# ghc-silk.net
KiCad netlist of a schematic drawn in EAGLE
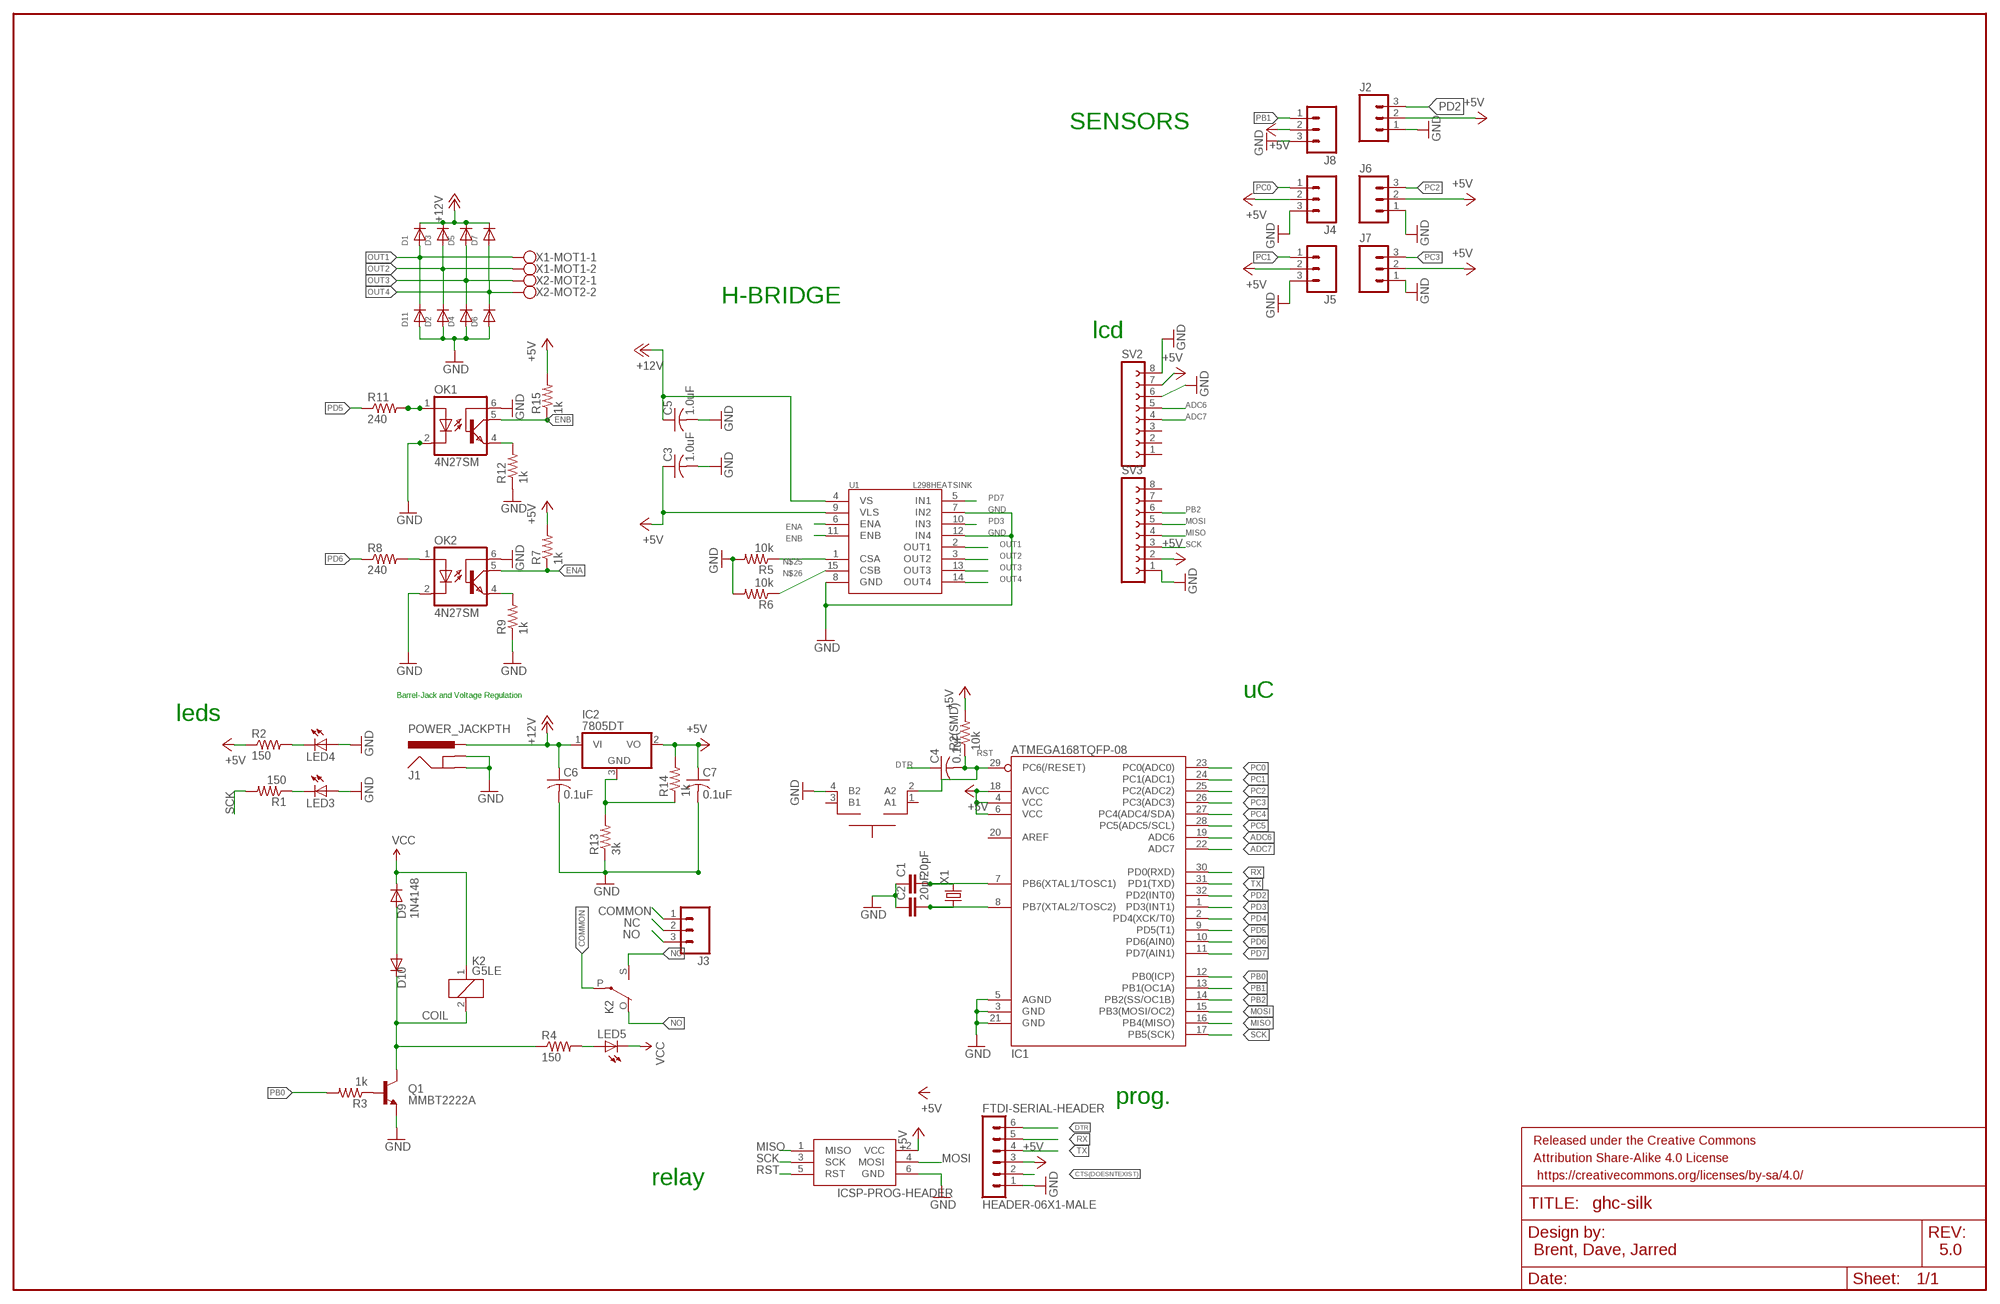
[diagram p0: schematic, sheet 1]

(export (version "E")
  (design (tool "Eeschema 10.0.6"))
  (components
    (comp (ref "C1")
      (value "20pF")
      (footprint "eagle-import:C0805")
      (libsource (lib "eagle-import") (part "C-EUC0805"))
    )
    (comp (ref "C2")
      (value "20pF")
      (footprint "eagle-import:C0805")
      (libsource (lib "eagle-import") (part "C-EUC0805"))
    )
    (comp (ref "C3")
      (value "1.0uF")
      (footprint "eagle-import:C0805")
      (libsource (lib "eagle-import") (part "C-USC0805"))
    )
    (comp (ref "C4")
      (value "0.1uF")
      (footprint "eagle-import:C0805")
      (libsource (lib "eagle-import") (part "C-USC0805"))
    )
    (comp (ref "C5")
      (value "1.0uF")
      (footprint "eagle-import:C0805")
      (libsource (lib "eagle-import") (part "C-USC0805"))
    )
    (comp (ref "C6")
      (value "0.1uF")
      (footprint "eagle-import:C0805")
      (libsource (lib "eagle-import") (part "C-USC0805"))
    )
    (comp (ref "C7")
      (value "0.1uF")
      (footprint "eagle-import:C0805")
      (libsource (lib "eagle-import") (part "C-USC0805"))
    )
    (comp (ref "D1")
      (value "DIODESOD-523")
      (footprint "eagle-import:SOD-523")
      (libsource (lib "eagle-import") (part "DIODESOD-523"))
    )
    (comp (ref "D2")
      (value "DIODESOD-523")
      (footprint "eagle-import:SOD-523")
      (libsource (lib "eagle-import") (part "DIODESOD-523"))
    )
    (comp (ref "D3")
      (value "DIODESOD-523")
      (footprint "eagle-import:SOD-523")
      (libsource (lib "eagle-import") (part "DIODESOD-523"))
    )
    (comp (ref "D4")
      (value "DIODESOD-523")
      (footprint "eagle-import:SOD-523")
      (libsource (lib "eagle-import") (part "DIODESOD-523"))
    )
    (comp (ref "D5")
      (value "DIODESOD-523")
      (footprint "eagle-import:SOD-523")
      (libsource (lib "eagle-import") (part "DIODESOD-523"))
    )
    (comp (ref "D6")
      (value "DIODESOD-523")
      (footprint "eagle-import:SOD-523")
      (libsource (lib "eagle-import") (part "DIODESOD-523"))
    )
    (comp (ref "D7")
      (value "DIODESOD-523")
      (footprint "eagle-import:SOD-523")
      (libsource (lib "eagle-import") (part "DIODESOD-523"))
    )
    (comp (ref "D9")
      (value "1N4148")
      (footprint "eagle-import:SOD-323F")
      (libsource (lib "eagle-import") (part "DIODESOD-323F"))
    )
    (comp (ref "D10")
      (value "Zener")
      (footprint "eagle-import:SOD-323F")
      (libsource (lib "eagle-import") (part "DIODESOD-323F"))
    )
    (comp (ref "D11")
      (value "DIODESOD-523")
      (footprint "eagle-import:SOD-523")
      (libsource (lib "eagle-import") (part "DIODESOD-523"))
    )
    (comp (ref "FRAME1")
      (value "FRAME-LEDGER")
      (footprint "eagle-import:CREATIVE_COMMONS")
      (libsource (lib "eagle-import") (part "FRAME-LEDGER"))
    )
    (comp (ref "FTDI-SERIAL-HEADER")
      (value "HEADER-06X1-MALE")
      (footprint "eagle-import:06X1-PTH")
      (libsource (lib "eagle-import") (part "HEADER-06X1?-MALE"))
    )
    (comp (ref "IC1")
      (value "ATMEGA168TQFP-08")
      (footprint "eagle-import:TQFP32-08")
      (libsource (lib "eagle-import") (part "ATMEGA168TQFP-08"))
    )
    (comp (ref "IC2")
      (value "7805DT")
      (footprint "eagle-import:TO252")
      (libsource (lib "eagle-import") (part "78DT05"))
    )
    (comp (ref "ICSP-PROG-HEADER")
      (value "AVRISP-6")
      (footprint "eagle-import:AVRISP")
      (libsource (lib "eagle-import") (part "AVRISP-6"))
    )
    (comp (ref "J1")
      (value "POWER_JACKPTH")
      (footprint "eagle-import:POWER_JACK_PTH")
      (libsource (lib "eagle-import") (part "POWER_JACKPTH"))
    )
    (comp (ref "J2")
      (value "M03SCREW_LOCK")
      (footprint "eagle-import:SCREWTERMINAL-3.5MM-3_LOCK.007S")
      (libsource (lib "eagle-import") (part "M03SCREW_LOCK"))
    )
    (comp (ref "J3")
      (value "M03-SCREW-5MM")
      (footprint "eagle-import:SCREWTERMINAL-5MM-3")
      (libsource (lib "eagle-import") (part "M03-SCREW-5MM"))
    )
    (comp (ref "J4")
      (value "M03SCREW_LOCK")
      (footprint "eagle-import:SCREWTERMINAL-3.5MM-3_LOCK.007S")
      (libsource (lib "eagle-import") (part "M03SCREW_LOCK"))
    )
    (comp (ref "J5")
      (value "M03SCREW_LOCK")
      (footprint "eagle-import:SCREWTERMINAL-3.5MM-3_LOCK.007S")
      (libsource (lib "eagle-import") (part "M03SCREW_LOCK"))
    )
    (comp (ref "J6")
      (value "M03SCREW_LOCK")
      (footprint "eagle-import:SCREWTERMINAL-3.5MM-3_LOCK.007S")
      (libsource (lib "eagle-import") (part "M03SCREW_LOCK"))
    )
    (comp (ref "J7")
      (value "M03SCREW_LOCK")
      (footprint "eagle-import:SCREWTERMINAL-3.5MM-3_LOCK.007S")
      (libsource (lib "eagle-import") (part "M03SCREW_LOCK"))
    )
    (comp (ref "J8")
      (value "M03SCREW_LOCK")
      (footprint "eagle-import:SCREWTERMINAL-3.5MM-3_LOCK.007S")
      (libsource (lib "eagle-import") (part "M03SCREW_LOCK"))
    )
    (comp (ref "K2")
      (value "G5LE")
      (footprint "eagle-import:G5LE")
      (libsource (lib "eagle-import") (part "G5LE"))
    )
    (comp (ref "LED3")
      (value "LEDCHIP-LED0805")
      (footprint "eagle-import:CHIP-LED0805")
      (libsource (lib "eagle-import") (part "LEDCHIP-LED0805"))
    )
    (comp (ref "LED4")
      (value "LEDCHIP-LED0805")
      (footprint "eagle-import:CHIP-LED0805")
      (libsource (lib "eagle-import") (part "LEDCHIP-LED0805"))
    )
    (comp (ref "LED5")
      (value "LEDCHIP-LED0805")
      (footprint "eagle-import:CHIP-LED0805")
      (libsource (lib "eagle-import") (part "LEDCHIP-LED0805"))
    )
    (comp (ref "OK1")
      (value "4N27SM")
      (footprint "eagle-import:DIL6-SMD")
      (fields (field (name "MF") "FAIRCHILD SEMICONDUCTOR") (field (name "MPN") "4N27S-M"))
      (libsource (lib "eagle-import") (part "4N?MS27"))
    )
    (comp (ref "OK2")
      (value "4N27SM")
      (footprint "eagle-import:DIL6-SMD")
      (fields (field (name "MF") "FAIRCHILD SEMICONDUCTOR") (field (name "MPN") "4N27S-M"))
      (libsource (lib "eagle-import") (part "4N?MS27"))
    )
    (comp (ref "Q1")
      (value "MMBT2222A")
      (footprint "eagle-import:SOT23-3")
      (libsource (lib "eagle-import") (part "TRANSISTOR_NPNMMBT2222A"))
    )
    (comp (ref "R1")
      (value "150")
      (footprint "eagle-import:M0805")
      (libsource (lib "eagle-import") (part "R-US_M0805"))
    )
    (comp (ref "R2")
      (value "150")
      (footprint "eagle-import:M0805")
      (libsource (lib "eagle-import") (part "R-US_M0805"))
    )
    (comp (ref "R2(SMD)")
      (value "10k")
      (footprint "eagle-import:M0805")
      (libsource (lib "eagle-import") (part "R-US_M0805"))
    )
    (comp (ref "R3")
      (value "1k")
      (footprint "eagle-import:M0805")
      (libsource (lib "eagle-import") (part "R-US_M0805"))
    )
    (comp (ref "R4")
      (value "150")
      (footprint "eagle-import:M0805")
      (libsource (lib "eagle-import") (part "R-US_M0805"))
    )
    (comp (ref "R5")
      (value "10k")
      (footprint "eagle-import:M0805")
      (libsource (lib "eagle-import") (part "R-US_M0805"))
    )
    (comp (ref "R6")
      (value "10k")
      (footprint "eagle-import:M0805")
      (libsource (lib "eagle-import") (part "R-US_M0805"))
    )
    (comp (ref "R7")
      (value "1k")
      (footprint "eagle-import:M0805")
      (libsource (lib "eagle-import") (part "R-US_M0805"))
    )
    (comp (ref "R8")
      (value "240")
      (footprint "eagle-import:M0805")
      (libsource (lib "eagle-import") (part "R-US_M0805"))
    )
    (comp (ref "R9")
      (value "1k")
      (footprint "eagle-import:M0805")
      (libsource (lib "eagle-import") (part "R-US_M0805"))
    )
    (comp (ref "R11")
      (value "240")
      (footprint "eagle-import:M0805")
      (libsource (lib "eagle-import") (part "R-US_M0805"))
    )
    (comp (ref "R12")
      (value "1k")
      (footprint "eagle-import:M0805")
      (libsource (lib "eagle-import") (part "R-US_M0805"))
    )
    (comp (ref "R13")
      (value "3k")
      (footprint "eagle-import:0402-RES")
      (libsource (lib "eagle-import") (part "RESISTOR0402"))
    )
    (comp (ref "R14")
      (value "1k")
      (footprint "eagle-import:M0805")
      (libsource (lib "eagle-import") (part "R-US_M0805"))
    )
    (comp (ref "R15")
      (value "1k")
      (footprint "eagle-import:M0805")
      (libsource (lib "eagle-import") (part "R-US_M0805"))
    )
    (comp (ref "SV2")
      (value "FE08-1")
      (footprint "eagle-import:FE08")
      (libsource (lib "eagle-import") (part "FE08-1"))
    )
    (comp (ref "SV3")
      (value "FE08-1")
      (footprint "eagle-import:FE08")
      (libsource (lib "eagle-import") (part "FE08-1"))
    )
    (comp (ref "SW2")
      (value "MOMENTARYBUTTON")
      (footprint "eagle-import:SPST_NO_SMD")
      (libsource (lib "eagle-import") (part "MOMENTARYBUTTON"))
    )
    (comp (ref "U1")
      (value "L298HEATSINK")
      (footprint "eagle-import:MULTIWATT15_6400BGHEATSINK")
      (libsource (lib "eagle-import") (part "L298HEATSINK"))
    )
    (comp (ref "X1")
      (value "CRYSTALHC49UP")
      (footprint "eagle-import:HC49UP")
      (libsource (lib "eagle-import") (part "CRYSTALHC49UP"))
    )
    (comp (ref "X1-MOT1")
      (value "W237-102")
      (footprint "eagle-import:W237-102")
      (fields (field (name "MPN") "237-102"))
      (libsource (lib "eagle-import") (part "W237-102"))
    )
    (comp (ref "X2-MOT2")
      (value "W237-102")
      (footprint "eagle-import:W237-102")
      (fields (field (name "MPN") "237-102"))
      (libsource (lib "eagle-import") (part "W237-102"))
    )
  )
  (nets
    (net (code "1") (name "+5V") (class "Default")
      (node (ref "C3") (pin "1") (pinfunction "1_1") (pintype "passive"))
      (node (ref "C7") (pin "1") (pinfunction "1_1") (pintype "passive"))
      (node (ref "FTDI-SERIAL-HEADER") (pin "3") (pinfunction "3_3") (pintype "passive"))
      (node (ref "IC1") (pin "18") (pinfunction "AVCC_18") (pintype "bidirectional"))
      (node (ref "IC1") (pin "4") (pinfunction "VCC_4") (pintype "bidirectional"))
      (node (ref "IC1") (pin "6") (pinfunction "VCC_6") (pintype "bidirectional"))
      (node (ref "IC2") (pin "2") (pinfunction "VO_2") (pintype "passive"))
      (node (ref "ICSP-PROG-HEADER") (pin "2") (pinfunction "VCC_2") (pintype "power_in"))
      (node (ref "J2") (pin "2") (pinfunction "2_2") (pintype "passive"))
      (node (ref "J4") (pin "2") (pinfunction "2_2") (pintype "passive"))
      (node (ref "J5") (pin "2") (pinfunction "2_2") (pintype "passive"))
      (node (ref "J6") (pin "2") (pinfunction "2_2") (pintype "passive"))
      (node (ref "J7") (pin "2") (pinfunction "2_2") (pintype "passive"))
      (node (ref "J8") (pin "2") (pinfunction "2_2") (pintype "passive"))
      (node (ref "R14") (pin "2") (pinfunction "2_2") (pintype "passive"))
      (node (ref "R15") (pin "2") (pinfunction "2_2") (pintype "passive"))
      (node (ref "R2") (pin "1") (pinfunction "1_1") (pintype "passive"))
      (node (ref "R2(SMD)") (pin "2") (pinfunction "2_2") (pintype "passive"))
      (node (ref "R7") (pin "2") (pinfunction "2_2") (pintype "passive"))
      (node (ref "SV2") (pin "7") (pinfunction "7_7") (pintype "passive"))
      (node (ref "SV3") (pin "2") (pinfunction "2_2") (pintype "passive"))
      (node (ref "U1") (pin "9") (pinfunction "VLS_9") (pintype "bidirectional"))
    )
    (net (code "2") (name "+12V") (class "Default")
      (node (ref "C5") (pin "1") (pinfunction "1_1") (pintype "passive"))
      (node (ref "C6") (pin "1") (pinfunction "1_1") (pintype "passive"))
      (node (ref "D1") (pin "K") (pinfunction "C_K") (pintype "passive"))
      (node (ref "D3") (pin "K") (pinfunction "C_K") (pintype "passive"))
      (node (ref "D5") (pin "K") (pinfunction "C_K") (pintype "passive"))
      (node (ref "D7") (pin "K") (pinfunction "C_K") (pintype "passive"))
      (node (ref "IC2") (pin "1") (pinfunction "VI_1") (pintype "input"))
      (node (ref "J1") (pin "PWR") (pinfunction "PWR_PWR") (pintype "bidirectional"))
      (node (ref "U1") (pin "4") (pinfunction "VS_4") (pintype "bidirectional"))
    )
    (net (code "3") (name "/COIL") (class "Default")
      (node (ref "D10") (pin "C") (pinfunction "C_C") (pintype "passive"))
      (node (ref "K2") (pin "2") (pinfunction "2_2") (pintype "passive"))
      (node (ref "Q1") (pin "3") (pinfunction "C_3") (pintype "passive"))
      (node (ref "R4") (pin "1") (pinfunction "1_1") (pintype "passive"))
    )
    (net (code "4") (name "/N$25") (class "Default")
      (node (ref "R5") (pin "1") (pinfunction "1_1") (pintype "passive"))
      (node (ref "U1") (pin "1") (pinfunction "CSA_1") (pintype "bidirectional"))
    )
    (net (code "5") (name "/N$26") (class "Default")
      (node (ref "R6") (pin "1") (pinfunction "1_1") (pintype "passive"))
      (node (ref "U1") (pin "15") (pinfunction "CSB_15") (pintype "bidirectional"))
    )
    (net (code "6") (name "/RST") (class "Default")
      (node (ref "C4") (pin "2") (pinfunction "2_2") (pintype "passive"))
      (node (ref "IC1") (pin "29") (pinfunction "PC6(/RESET)_29") (pintype "bidirectional"))
      (node (ref "ICSP-PROG-HEADER") (pin "5") (pinfunction "RST_5") (pintype "output"))
      (node (ref "R2(SMD)") (pin "1") (pinfunction "1_1") (pintype "passive"))
      (node (ref "SW2") (pin "2") (pinfunction "A2_2") (pintype "bidirectional"))
    )
    (net (code "7") (name "ADC6") (class "Default")
      (node (ref "IC1") (pin "19") (pinfunction "ADC6_19") (pintype "bidirectional"))
      (node (ref "SV2") (pin "5") (pinfunction "5_5") (pintype "passive"))
    )
    (net (code "8") (name "ADC7") (class "Default")
      (node (ref "IC1") (pin "22") (pinfunction "ADC7_22") (pintype "bidirectional"))
      (node (ref "SV2") (pin "4") (pinfunction "4_4") (pintype "passive"))
    )
    (net (code "9") (name "COMMON") (class "Default")
      (node (ref "J3") (pin "1") (pinfunction "1_1") (pintype "passive"))
      (node (ref "K2") (pin "P") (pinfunction "P_P") (pintype "passive"))
    )
    (net (code "10") (name "CTS(DOESNTEXIST)") (class "Default")
      (node (ref "FTDI-SERIAL-HEADER") (pin "2") (pinfunction "2_2") (pintype "passive"))
    )
    (net (code "11") (name "DTR") (class "Default")
      (node (ref "C4") (pin "1") (pinfunction "1_1") (pintype "passive"))
      (node (ref "FTDI-SERIAL-HEADER") (pin "6") (pinfunction "6_6") (pintype "passive"))
    )
    (net (code "12") (name "ENA") (class "Default")
      (node (ref "OK2") (pin "5") (pinfunction "COL_5") (pintype "passive"))
      (node (ref "R7") (pin "1") (pinfunction "1_1") (pintype "passive"))
      (node (ref "U1") (pin "6") (pinfunction "ENA_6") (pintype "bidirectional"))
    )
    (net (code "13") (name "ENB") (class "Default")
      (node (ref "OK1") (pin "5") (pinfunction "COL_5") (pintype "passive"))
      (node (ref "R15") (pin "1") (pinfunction "1_1") (pintype "passive"))
      (node (ref "U1") (pin "11") (pinfunction "ENB_11") (pintype "bidirectional"))
    )
    (net (code "14") (name "GND") (class "Default")
      (node (ref "C1") (pin "1") (pinfunction "1_1") (pintype "passive"))
      (node (ref "C2") (pin "1") (pinfunction "1_1") (pintype "passive"))
      (node (ref "C3") (pin "2") (pinfunction "2_2") (pintype "passive"))
      (node (ref "C5") (pin "2") (pinfunction "2_2") (pintype "passive"))
      (node (ref "C6") (pin "2") (pinfunction "2_2") (pintype "passive"))
      (node (ref "C7") (pin "2") (pinfunction "2_2") (pintype "passive"))
      (node (ref "D11") (pin "A") (pinfunction "A_A") (pintype "passive"))
      (node (ref "D2") (pin "A") (pinfunction "A_A") (pintype "passive"))
      (node (ref "D4") (pin "A") (pinfunction "A_A") (pintype "passive"))
      (node (ref "D6") (pin "A") (pinfunction "A_A") (pintype "passive"))
      (node (ref "FTDI-SERIAL-HEADER") (pin "1") (pinfunction "1_1") (pintype "passive"))
      (node (ref "IC1") (pin "21") (pinfunction "GND_21") (pintype "bidirectional"))
      (node (ref "IC1") (pin "3") (pinfunction "GND_3") (pintype "bidirectional"))
      (node (ref "IC1") (pin "5") (pinfunction "AGND_5") (pintype "bidirectional"))
      (node (ref "ICSP-PROG-HEADER") (pin "6") (pinfunction "GND_6") (pintype "power_in"))
      (node (ref "J1") (pin "GND") (pinfunction "GND_GND") (pintype "bidirectional"))
      (node (ref "J1") (pin "GNDBREAK") (pinfunction "GNDBREAK_GNDBREAK") (pintype "bidirectional"))
      (node (ref "J2") (pin "1") (pinfunction "1_1") (pintype "passive"))
      (node (ref "J4") (pin "3") (pinfunction "3_3") (pintype "passive"))
      (node (ref "J5") (pin "3") (pinfunction "3_3") (pintype "passive"))
      (node (ref "J6") (pin "1") (pinfunction "1_1") (pintype "passive"))
      (node (ref "J7") (pin "1") (pinfunction "1_1") (pintype "passive"))
      (node (ref "J8") (pin "3") (pinfunction "3_3") (pintype "passive"))
      (node (ref "LED3") (pin "A") (pinfunction "A_A") (pintype "passive"))
      (node (ref "LED4") (pin "A") (pinfunction "A_A") (pintype "passive"))
      (node (ref "OK1") (pin "2") (pinfunction "C_2") (pintype "passive"))
      (node (ref "OK1") (pin "6") (pinfunction "BAS_6") (pintype "passive"))
      (node (ref "OK2") (pin "2") (pinfunction "C_2") (pintype "passive"))
      (node (ref "OK2") (pin "6") (pinfunction "BAS_6") (pintype "passive"))
      (node (ref "Q1") (pin "2") (pinfunction "E_2") (pintype "passive"))
      (node (ref "R12") (pin "1") (pinfunction "1_1") (pintype "passive"))
      (node (ref "R13") (pin "1") (pinfunction "1_1") (pintype "passive"))
      (node (ref "R5") (pin "2") (pinfunction "2_2") (pintype "passive"))
      (node (ref "R6") (pin "2") (pinfunction "2_2") (pintype "passive"))
      (node (ref "R9") (pin "1") (pinfunction "1_1") (pintype "passive"))
      (node (ref "SV2") (pin "6") (pinfunction "6_6") (pintype "passive"))
      (node (ref "SV2") (pin "8") (pinfunction "8_8") (pintype "passive"))
      (node (ref "SV3") (pin "1") (pinfunction "1_1") (pintype "passive"))
      (node (ref "SW2") (pin "4") (pinfunction "B2_4") (pintype "bidirectional"))
      (node (ref "U1") (pin "12") (pinfunction "IN4_12") (pintype "bidirectional"))
      (node (ref "U1") (pin "7") (pinfunction "IN2_7") (pintype "bidirectional"))
      (node (ref "U1") (pin "8") (pinfunction "GND_8") (pintype "bidirectional"))
    )
    (net (code "15") (name "MISO") (class "Default")
      (node (ref "IC1") (pin "16") (pinfunction "PB4(MISO)_16") (pintype "bidirectional"))
      (node (ref "ICSP-PROG-HEADER") (pin "1") (pinfunction "MISO_1") (pintype "input"))
      (node (ref "SV3") (pin "4") (pinfunction "4_4") (pintype "passive"))
    )
    (net (code "16") (name "MOSI") (class "Default")
      (node (ref "IC1") (pin "15") (pinfunction "PB3(MOSI/OC2)_15") (pintype "bidirectional"))
      (node (ref "ICSP-PROG-HEADER") (pin "4") (pinfunction "MOSI_4") (pintype "output"))
      (node (ref "SV3") (pin "5") (pinfunction "5_5") (pintype "passive"))
    )
    (net (code "17") (name "NC") (class "Default")
      (node (ref "J3") (pin "2") (pinfunction "2_2") (pintype "passive"))
      (node (ref "K2") (pin "S") (pinfunction "S_S") (pintype "passive"))
    )
    (net (code "18") (name "NO") (class "Default")
      (node (ref "J3") (pin "3") (pinfunction "3_3") (pintype "passive"))
      (node (ref "K2") (pin "O") (pinfunction "O_O") (pintype "passive"))
    )
    (net (code "19") (name "Net-(D10-PadA)") (class "Default")
      (node (ref "D10") (pin "A") (pinfunction "A_A") (pintype "passive"))
      (node (ref "D9") (pin "A") (pinfunction "A_A") (pintype "passive"))
    )
    (net (code "20") (name "Net-(IC1-PB6(XTAL1{slash}TOSC1))") (class "Default")
      (node (ref "C1") (pin "2") (pinfunction "2_2") (pintype "passive"))
      (node (ref "IC1") (pin "7") (pinfunction "PB6(XTAL1/TOSC1)_7") (pintype "bidirectional"))
      (node (ref "X1") (pin "2") (pinfunction "2_2") (pintype "passive"))
    )
    (net (code "21") (name "Net-(IC1-PB7(XTAL2{slash}TOSC2))") (class "Default")
      (node (ref "C2") (pin "2") (pinfunction "2_2") (pintype "passive"))
      (node (ref "IC1") (pin "8") (pinfunction "PB7(XTAL2/TOSC2)_8") (pintype "bidirectional"))
      (node (ref "X1") (pin "1") (pinfunction "1_1") (pintype "passive"))
    )
    (net (code "22") (name "Net-(IC2-GND)") (class "Default")
      (node (ref "IC2") (pin "3") (pinfunction "GND_3") (pintype "passive"))
      (node (ref "R13") (pin "2") (pinfunction "2_2") (pintype "passive"))
      (node (ref "R14") (pin "1") (pinfunction "1_1") (pintype "passive"))
    )
    (net (code "23") (name "Net-(LED3-PadC)") (class "Default")
      (node (ref "LED3") (pin "C") (pinfunction "C_C") (pintype "passive"))
      (node (ref "R1") (pin "1") (pinfunction "1_1") (pintype "passive"))
    )
    (net (code "24") (name "Net-(LED4-PadC)") (class "Default")
      (node (ref "LED4") (pin "C") (pinfunction "C_C") (pintype "passive"))
      (node (ref "R2") (pin "2") (pinfunction "2_2") (pintype "passive"))
    )
    (net (code "25") (name "Net-(LED5-PadA)") (class "Default")
      (node (ref "LED5") (pin "A") (pinfunction "A_A") (pintype "passive"))
      (node (ref "R4") (pin "2") (pinfunction "2_2") (pintype "passive"))
    )
    (net (code "26") (name "Net-(OK1-A)") (class "Default")
      (node (ref "OK1") (pin "1") (pinfunction "A_1") (pintype "passive"))
      (node (ref "R11") (pin "2") (pinfunction "2_2") (pintype "passive"))
    )
    (net (code "27") (name "Net-(OK1-EMI)") (class "Default")
      (node (ref "OK1") (pin "4") (pinfunction "EMI_4") (pintype "passive"))
      (node (ref "R12") (pin "2") (pinfunction "2_2") (pintype "passive"))
    )
    (net (code "28") (name "Net-(OK2-A)") (class "Default")
      (node (ref "OK2") (pin "1") (pinfunction "A_1") (pintype "passive"))
      (node (ref "R8") (pin "2") (pinfunction "2_2") (pintype "passive"))
    )
    (net (code "29") (name "Net-(OK2-EMI)") (class "Default")
      (node (ref "OK2") (pin "4") (pinfunction "EMI_4") (pintype "passive"))
      (node (ref "R9") (pin "2") (pinfunction "2_2") (pintype "passive"))
    )
    (net (code "30") (name "Net-(Q1-B)") (class "Default")
      (node (ref "Q1") (pin "1") (pinfunction "B_1") (pintype "passive"))
      (node (ref "R3") (pin "1") (pinfunction "1_1") (pintype "passive"))
    )
    (net (code "31") (name "OUT1") (class "Default")
      (node (ref "D1") (pin "A") (pinfunction "A_A") (pintype "passive"))
      (node (ref "D11") (pin "K") (pinfunction "C_K") (pintype "passive"))
      (node (ref "U1") (pin "2") (pinfunction "OUT1_2") (pintype "bidirectional"))
      (node (ref "X1-MOT1") (pin "1") (pinfunction "KL_1") (pintype "passive"))
    )
    (net (code "32") (name "OUT2") (class "Default")
      (node (ref "D2") (pin "K") (pinfunction "C_K") (pintype "passive"))
      (node (ref "D3") (pin "A") (pinfunction "A_A") (pintype "passive"))
      (node (ref "U1") (pin "3") (pinfunction "OUT2_3") (pintype "bidirectional"))
      (node (ref "X1-MOT1") (pin "2") (pinfunction "KL_2") (pintype "passive"))
    )
    (net (code "33") (name "OUT3") (class "Default")
      (node (ref "D4") (pin "K") (pinfunction "C_K") (pintype "passive"))
      (node (ref "D5") (pin "A") (pinfunction "A_A") (pintype "passive"))
      (node (ref "U1") (pin "13") (pinfunction "OUT3_13") (pintype "bidirectional"))
      (node (ref "X2-MOT2") (pin "1") (pinfunction "KL_1") (pintype "passive"))
    )
    (net (code "34") (name "OUT4") (class "Default")
      (node (ref "D6") (pin "K") (pinfunction "C_K") (pintype "passive"))
      (node (ref "D7") (pin "A") (pinfunction "A_A") (pintype "passive"))
      (node (ref "U1") (pin "14") (pinfunction "OUT4_14") (pintype "bidirectional"))
      (node (ref "X2-MOT2") (pin "2") (pinfunction "KL_2") (pintype "passive"))
    )
    (net (code "35") (name "PB0") (class "Default")
      (node (ref "IC1") (pin "12") (pinfunction "PB0(ICP)_12") (pintype "bidirectional"))
      (node (ref "R3") (pin "2") (pinfunction "2_2") (pintype "passive"))
    )
    (net (code "36") (name "PB1") (class "Default")
      (node (ref "IC1") (pin "13") (pinfunction "PB1(OC1A)_13") (pintype "bidirectional"))
      (node (ref "J8") (pin "1") (pinfunction "1_1") (pintype "passive"))
    )
    (net (code "37") (name "PB2") (class "Default")
      (node (ref "IC1") (pin "14") (pinfunction "PB2(SS/OC1B)_14") (pintype "bidirectional"))
      (node (ref "SV3") (pin "6") (pinfunction "6_6") (pintype "passive"))
    )
    (net (code "38") (name "PC0") (class "Default")
      (node (ref "IC1") (pin "23") (pinfunction "PC0(ADC0)_23") (pintype "bidirectional"))
      (node (ref "J4") (pin "1") (pinfunction "1_1") (pintype "passive"))
    )
    (net (code "39") (name "PC1") (class "Default")
      (node (ref "IC1") (pin "24") (pinfunction "PC1(ADC1)_24") (pintype "bidirectional"))
      (node (ref "J5") (pin "1") (pinfunction "1_1") (pintype "passive"))
    )
    (net (code "40") (name "PC2") (class "Default")
      (node (ref "IC1") (pin "25") (pinfunction "PC2(ADC2)_25") (pintype "bidirectional"))
      (node (ref "J6") (pin "3") (pinfunction "3_3") (pintype "passive"))
    )
    (net (code "41") (name "PC3") (class "Default")
      (node (ref "IC1") (pin "26") (pinfunction "PC3(ADC3)_26") (pintype "bidirectional"))
      (node (ref "J7") (pin "3") (pinfunction "3_3") (pintype "passive"))
    )
    (net (code "42") (name "PC4") (class "Default")
      (node (ref "IC1") (pin "27") (pinfunction "PC4(ADC4/SDA)_27") (pintype "bidirectional"))
    )
    (net (code "43") (name "PC5") (class "Default")
      (node (ref "IC1") (pin "28") (pinfunction "PC5(ADC5/SCL)_28") (pintype "bidirectional"))
    )
    (net (code "44") (name "PD2") (class "Default")
      (node (ref "IC1") (pin "32") (pinfunction "PD2(INT0)_32") (pintype "bidirectional"))
      (node (ref "J2") (pin "3") (pinfunction "3_3") (pintype "passive"))
    )
    (net (code "45") (name "PD3") (class "Default")
      (node (ref "IC1") (pin "1") (pinfunction "PD3(INT1)_1") (pintype "bidirectional"))
      (node (ref "U1") (pin "10") (pinfunction "IN3_10") (pintype "bidirectional"))
    )
    (net (code "46") (name "PD4") (class "Default")
      (node (ref "IC1") (pin "2") (pinfunction "PD4(XCK/T0)_2") (pintype "bidirectional"))
    )
    (net (code "47") (name "PD5") (class "Default")
      (node (ref "IC1") (pin "9") (pinfunction "PD5(T1)_9") (pintype "bidirectional"))
      (node (ref "R11") (pin "1") (pinfunction "1_1") (pintype "passive"))
    )
    (net (code "48") (name "PD6") (class "Default")
      (node (ref "IC1") (pin "10") (pinfunction "PD6(AIN0)_10") (pintype "bidirectional"))
      (node (ref "R8") (pin "1") (pinfunction "1_1") (pintype "passive"))
    )
    (net (code "49") (name "PD7") (class "Default")
      (node (ref "IC1") (pin "11") (pinfunction "PD7(AIN1)_11") (pintype "bidirectional"))
      (node (ref "U1") (pin "5") (pinfunction "IN1_5") (pintype "bidirectional"))
    )
    (net (code "50") (name "RX") (class "Default")
      (node (ref "FTDI-SERIAL-HEADER") (pin "5") (pinfunction "5_5") (pintype "passive"))
      (node (ref "IC1") (pin "30") (pinfunction "PD0(RXD)_30") (pintype "bidirectional"))
    )
    (net (code "51") (name "SCK") (class "Default")
      (node (ref "IC1") (pin "17") (pinfunction "PB5(SCK)_17") (pintype "bidirectional"))
      (node (ref "ICSP-PROG-HEADER") (pin "3") (pinfunction "SCK_3") (pintype "output"))
      (node (ref "R1") (pin "2") (pinfunction "2_2") (pintype "passive"))
      (node (ref "SV3") (pin "3") (pinfunction "3_3") (pintype "passive"))
    )
    (net (code "52") (name "TX") (class "Default")
      (node (ref "FTDI-SERIAL-HEADER") (pin "4") (pinfunction "4_4") (pintype "passive"))
      (node (ref "IC1") (pin "31") (pinfunction "PD1(TXD)_31") (pintype "bidirectional"))
    )
    (net (code "53") (name "VCC") (class "Default")
      (node (ref "D9") (pin "C") (pinfunction "C_C") (pintype "passive"))
      (node (ref "K2") (pin "1") (pinfunction "1_1") (pintype "passive"))
      (node (ref "LED5") (pin "C") (pinfunction "C_C") (pintype "passive"))
    )
    (net (code "54") (name "unconnected-(IC1-AREF-Pad20)") (class "Default")
      (node (ref "IC1") (pin "20") (pinfunction "AREF_20") (pintype "bidirectional"))
    )
    (net (code "55") (name "unconnected-(SV2-Pad1)") (class "Default")
      (node (ref "SV2") (pin "1") (pinfunction "1_1") (pintype "passive"))
    )
    (net (code "56") (name "unconnected-(SV2-Pad2)") (class "Default")
      (node (ref "SV2") (pin "2") (pinfunction "2_2") (pintype "passive"))
    )
    (net (code "57") (name "unconnected-(SV2-Pad3)") (class "Default")
      (node (ref "SV2") (pin "3") (pinfunction "3_3") (pintype "passive"))
    )
    (net (code "58") (name "unconnected-(SV3-Pad7)") (class "Default")
      (node (ref "SV3") (pin "7") (pinfunction "7_7") (pintype "passive"))
    )
    (net (code "59") (name "unconnected-(SV3-Pad8)") (class "Default")
      (node (ref "SV3") (pin "8") (pinfunction "8_8") (pintype "passive"))
    )
    (net (code "60") (name "unconnected-(SW2-A1-Pad1)") (class "Default")
      (node (ref "SW2") (pin "1") (pinfunction "A1_1") (pintype "bidirectional"))
    )
    (net (code "61") (name "unconnected-(SW2-B1-Pad3)") (class "Default")
      (node (ref "SW2") (pin "3") (pinfunction "B1_3") (pintype "bidirectional"))
    )
  )
)
